# light.net
KiCad netlist of a schematic drawn in EAGLE
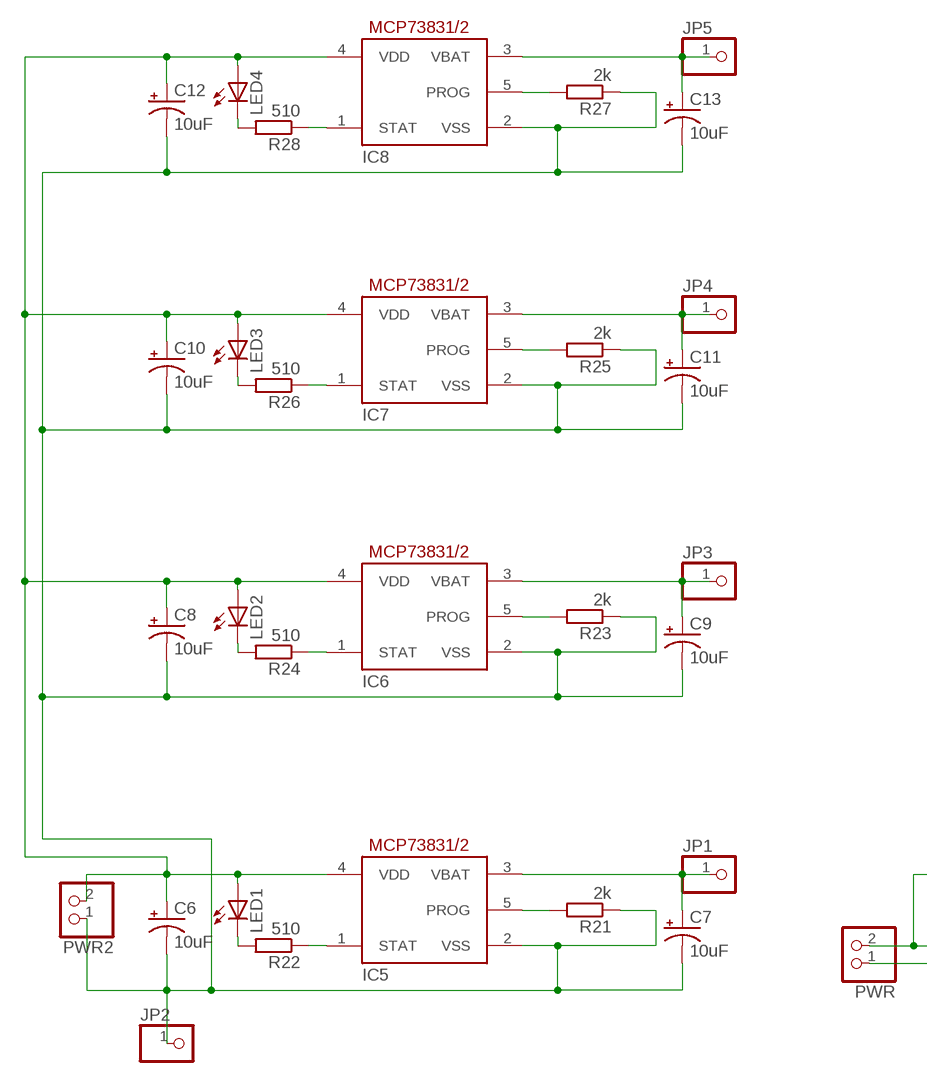
[diagram p0: schematic, sheet 1, part 1 of 2]
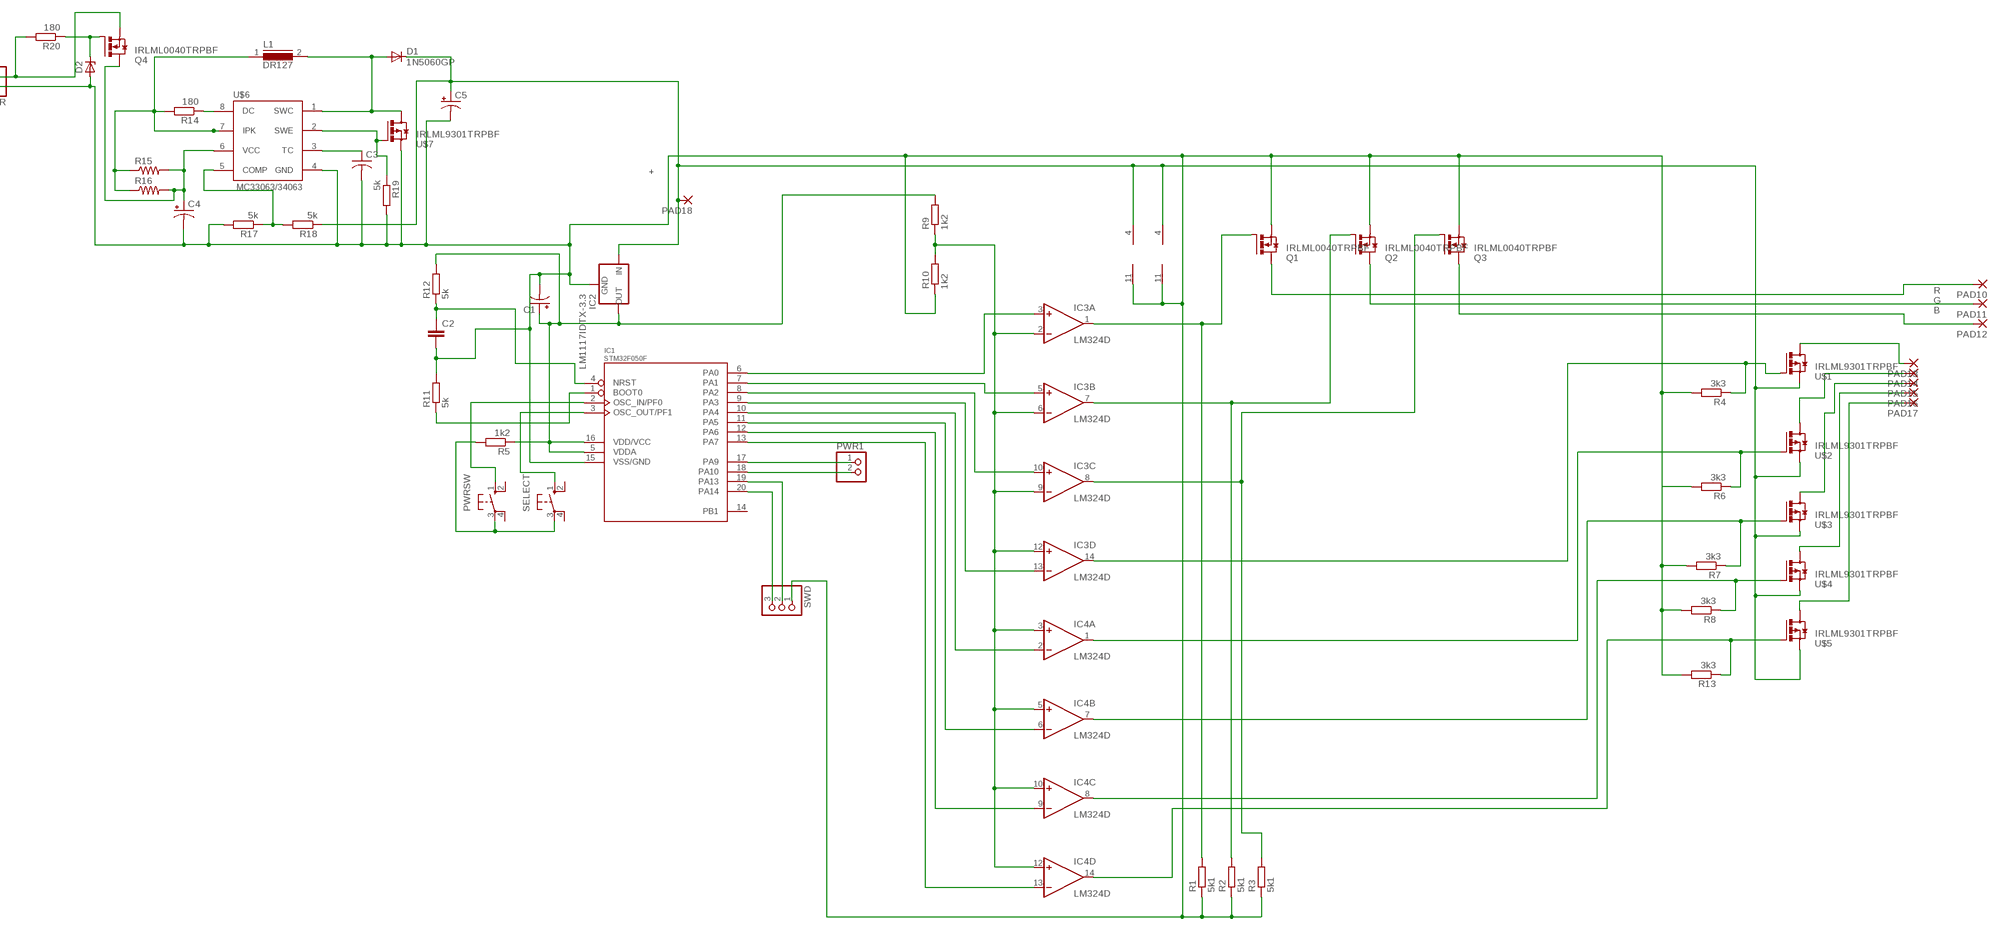
[diagram p1: schematic, sheet 1, part 2 of 2]

(export (version "E")
  (design (tool "Eeschema 10.0.6"))
  (components
    (comp (ref "C1")
      (value "CPOL-USSMCD")
      (footprint "eagle-import:SMC_D")
      (libsource (lib "eagle-import") (part "CPOL-USSMCD"))
    )
    (comp (ref "C2")
      (value "C-EUC1206")
      (footprint "eagle-import:C1206")
      (libsource (lib "eagle-import") (part "C-EUC1206"))
    )
    (comp (ref "C3")
      (value "C-US050-024X044")
      (footprint "eagle-import:C050-024X044")
      (libsource (lib "eagle-import") (part "C-US050-024X044"))
    )
    (comp (ref "C4")
      (value "CPOL-USE5-8.5")
      (footprint "eagle-import:E5-8,5")
      (libsource (lib "eagle-import") (part "CPOL-USE5-8.5"))
    )
    (comp (ref "C5")
      (value "CPOL-USE5-8.5")
      (footprint "eagle-import:E5-8,5")
      (libsource (lib "eagle-import") (part "CPOL-USE5-8.5"))
    )
    (comp (ref "C6")
      (value "10uF")
      (footprint "eagle-import:SMC_D")
      (libsource (lib "eagle-import") (part "CPOL-USSMCD"))
    )
    (comp (ref "C7")
      (value "10uF")
      (footprint "eagle-import:SMC_D")
      (libsource (lib "eagle-import") (part "CPOL-USSMCD"))
    )
    (comp (ref "C8")
      (value "10uF")
      (footprint "eagle-import:SMC_D")
      (libsource (lib "eagle-import") (part "CPOL-USSMCD"))
    )
    (comp (ref "C9")
      (value "10uF")
      (footprint "eagle-import:SMC_D")
      (libsource (lib "eagle-import") (part "CPOL-USSMCD"))
    )
    (comp (ref "C10")
      (value "10uF")
      (footprint "eagle-import:SMC_D")
      (libsource (lib "eagle-import") (part "CPOL-USSMCD"))
    )
    (comp (ref "C11")
      (value "10uF")
      (footprint "eagle-import:SMC_D")
      (libsource (lib "eagle-import") (part "CPOL-USSMCD"))
    )
    (comp (ref "C12")
      (value "10uF")
      (footprint "eagle-import:SMC_D")
      (libsource (lib "eagle-import") (part "CPOL-USSMCD"))
    )
    (comp (ref "C13")
      (value "10uF")
      (footprint "eagle-import:SMC_D")
      (libsource (lib "eagle-import") (part "CPOL-USSMCD"))
    )
    (comp (ref "D1")
      (value "1N5060GP")
      (footprint "eagle-import:DO15-12")
      (libsource (lib "eagle-import") (part "1N5060GP"))
    )
    (comp (ref "D2")
      (value "ZENER-DIODESOD80C")
      (footprint "eagle-import:SOD80C")
      (libsource (lib "eagle-import") (part "ZENER-DIODESOD80C"))
    )
    (comp (ref "IC1")
      (value "STM32F050F")
      (footprint "eagle-import:TSSOP20")
      (libsource (lib "eagle-import") (part "STM32F050F"))
    )
    (comp (ref "IC2")
      (value "LM1117IDTX-3.3")
      (footprint "eagle-import:TO252")
      (libsource (lib "eagle-import") (part "LM1117IDTX-3.3"))
    )
    (comp (ref "IC3")
      (value "LM324D")
      (footprint "eagle-import:SO14")
      (libsource (lib "eagle-import") (part "LM324D"))
    )
    (comp (ref "IC4")
      (value "LM324D")
      (footprint "eagle-import:SO14")
      (libsource (lib "eagle-import") (part "LM324D"))
    )
    (comp (ref "IC5")
      (value "MCP73831/OT")
      (footprint "eagle-import:SOT23-5L")
      (libsource (lib "eagle-import") (part "MCP73831/OT"))
    )
    (comp (ref "IC6")
      (value "MCP73831/OT")
      (footprint "eagle-import:SOT23-5L")
      (libsource (lib "eagle-import") (part "MCP73831/OT"))
    )
    (comp (ref "IC7")
      (value "MCP73831/OT")
      (footprint "eagle-import:SOT23-5L")
      (libsource (lib "eagle-import") (part "MCP73831/OT"))
    )
    (comp (ref "IC8")
      (value "MCP73831/OT")
      (footprint "eagle-import:SOT23-5L")
      (libsource (lib "eagle-import") (part "MCP73831/OT"))
    )
    (comp (ref "JP1")
      (value "PINHD-1X1")
      (footprint "eagle-import:1X01")
      (libsource (lib "eagle-import") (part "PINHD-1X1"))
    )
    (comp (ref "JP2")
      (value "PINHD-1X1")
      (footprint "eagle-import:1X01")
      (libsource (lib "eagle-import") (part "PINHD-1X1"))
    )
    (comp (ref "JP3")
      (value "PINHD-1X1")
      (footprint "eagle-import:1X01")
      (libsource (lib "eagle-import") (part "PINHD-1X1"))
    )
    (comp (ref "JP4")
      (value "PINHD-1X1")
      (footprint "eagle-import:1X01")
      (libsource (lib "eagle-import") (part "PINHD-1X1"))
    )
    (comp (ref "JP5")
      (value "PINHD-1X1")
      (footprint "eagle-import:1X01")
      (libsource (lib "eagle-import") (part "PINHD-1X1"))
    )
    (comp (ref "L1")
      (value "DR127")
      (footprint "eagle-import:DR127")
      (libsource (lib "eagle-import") (part "DR127"))
    )
    (comp (ref "LED1")
      (value "LED")
      (footprint "eagle-import:SMARTLED-TTW")
      (libsource (lib "eagle-import") (part "LED"))
    )
    (comp (ref "LED2")
      (value "LED")
      (footprint "eagle-import:SMARTLED-TTW")
      (libsource (lib "eagle-import") (part "LED"))
    )
    (comp (ref "LED3")
      (value "LED")
      (footprint "eagle-import:SMARTLED-TTW")
      (libsource (lib "eagle-import") (part "LED"))
    )
    (comp (ref "LED4")
      (value "LED")
      (footprint "eagle-import:SMARTLED-TTW")
      (libsource (lib "eagle-import") (part "LED"))
    )
    (comp (ref "PAD10")
      (value "SMD2")
      (footprint "eagle-import:SMD1,27-2,54")
      (libsource (lib "eagle-import") (part "SMD2"))
    )
    (comp (ref "PAD11")
      (value "SMD2")
      (footprint "eagle-import:SMD1,27-2,54")
      (libsource (lib "eagle-import") (part "SMD2"))
    )
    (comp (ref "PAD12")
      (value "SMD2")
      (footprint "eagle-import:SMD1,27-2,54")
      (libsource (lib "eagle-import") (part "SMD2"))
    )
    (comp (ref "PAD13")
      (value "SMD2")
      (footprint "eagle-import:SMD1,27-2,54")
      (libsource (lib "eagle-import") (part "SMD2"))
    )
    (comp (ref "PAD14")
      (value "SMD2")
      (footprint "eagle-import:SMD1,27-2,54")
      (libsource (lib "eagle-import") (part "SMD2"))
    )
    (comp (ref "PAD15")
      (value "SMD2")
      (footprint "eagle-import:SMD1,27-2,54")
      (libsource (lib "eagle-import") (part "SMD2"))
    )
    (comp (ref "PAD16")
      (value "SMD2")
      (footprint "eagle-import:SMD1,27-2,54")
      (libsource (lib "eagle-import") (part "SMD2"))
    )
    (comp (ref "PAD17")
      (value "SMD2")
      (footprint "eagle-import:SMD1,27-2,54")
      (libsource (lib "eagle-import") (part "SMD2"))
    )
    (comp (ref "PAD18")
      (value "SMD2")
      (footprint "eagle-import:SMD1,27-2,54")
      (libsource (lib "eagle-import") (part "SMD2"))
    )
    (comp (ref "PWR")
      (value "PINHD-1X2")
      (footprint "eagle-import:1X02")
      (libsource (lib "eagle-import") (part "PINHD-1X2"))
    )
    (comp (ref "PWR1")
      (value "PINHD-1X2")
      (footprint "eagle-import:1X02")
      (libsource (lib "eagle-import") (part "PINHD-1X2"))
    )
    (comp (ref "PWR2")
      (value "PINHD-1X2")
      (footprint "eagle-import:1X02")
      (libsource (lib "eagle-import") (part "PINHD-1X2"))
    )
    (comp (ref "PWRSW")
      (value "10-XX")
      (footprint "eagle-import:B3F-10XX")
      (fields (field (name "MPN") "B3F-1000"))
      (libsource (lib "eagle-import") (part "10-XX"))
    )
    (comp (ref "Q1")
      (value "IRLML0040TRPBF")
      (footprint "eagle-import:MICRO3")
      (libsource (lib "eagle-import") (part "IRLML0040TRPBF"))
    )
    (comp (ref "Q2")
      (value "IRLML0040TRPBF")
      (footprint "eagle-import:MICRO3")
      (libsource (lib "eagle-import") (part "IRLML0040TRPBF"))
    )
    (comp (ref "Q3")
      (value "IRLML0040TRPBF")
      (footprint "eagle-import:MICRO3")
      (libsource (lib "eagle-import") (part "IRLML0040TRPBF"))
    )
    (comp (ref "Q4")
      (value "IRLML0040TRPBF")
      (footprint "eagle-import:MICRO3")
      (libsource (lib "eagle-import") (part "IRLML0040TRPBF"))
    )
    (comp (ref "R1")
      (value "5k1")
      (footprint "eagle-import:M1206")
      (libsource (lib "eagle-import") (part "R-EU_M1206"))
    )
    (comp (ref "R2")
      (value "5k1")
      (footprint "eagle-import:M1206")
      (libsource (lib "eagle-import") (part "R-EU_M1206"))
    )
    (comp (ref "R3")
      (value "5k1")
      (footprint "eagle-import:M1206")
      (libsource (lib "eagle-import") (part "R-EU_M1206"))
    )
    (comp (ref "R4")
      (value "3k3")
      (footprint "eagle-import:M1206")
      (libsource (lib "eagle-import") (part "R-EU_M1206"))
    )
    (comp (ref "R5")
      (value "1k2")
      (footprint "eagle-import:M1206")
      (libsource (lib "eagle-import") (part "R-EU_M1206"))
    )
    (comp (ref "R6")
      (value "3k3")
      (footprint "eagle-import:M1206")
      (libsource (lib "eagle-import") (part "R-EU_M1206"))
    )
    (comp (ref "R7")
      (value "3k3")
      (footprint "eagle-import:M1206")
      (libsource (lib "eagle-import") (part "R-EU_M1206"))
    )
    (comp (ref "R8")
      (value "3k3")
      (footprint "eagle-import:M1206")
      (libsource (lib "eagle-import") (part "R-EU_M1206"))
    )
    (comp (ref "R9")
      (value "1k2")
      (footprint "eagle-import:M1206")
      (libsource (lib "eagle-import") (part "R-EU_M1206"))
    )
    (comp (ref "R10")
      (value "1k2")
      (footprint "eagle-import:M1206")
      (libsource (lib "eagle-import") (part "R-EU_M1206"))
    )
    (comp (ref "R11")
      (value "5k")
      (footprint "eagle-import:M1206")
      (libsource (lib "eagle-import") (part "R-EU_M1206"))
    )
    (comp (ref "R12")
      (value "5k")
      (footprint "eagle-import:M1206")
      (libsource (lib "eagle-import") (part "R-EU_M1206"))
    )
    (comp (ref "R13")
      (value "3k3")
      (footprint "eagle-import:M1206")
      (libsource (lib "eagle-import") (part "R-EU_M1206"))
    )
    (comp (ref "R14")
      (value "180")
      (footprint "eagle-import:M1206")
      (libsource (lib "eagle-import") (part "R-EU_M1206"))
    )
    (comp (ref "R15")
      (value "R-US_0207/12")
      (footprint "eagle-import:0207_12")
      (libsource (lib "eagle-import") (part "R-US_0207/12"))
    )
    (comp (ref "R16")
      (value "R-US_0207/12")
      (footprint "eagle-import:0207_12")
      (libsource (lib "eagle-import") (part "R-US_0207/12"))
    )
    (comp (ref "R17")
      (value "5k")
      (footprint "eagle-import:M1206")
      (libsource (lib "eagle-import") (part "R-EU_M1206"))
    )
    (comp (ref "R18")
      (value "5k")
      (footprint "eagle-import:M1206")
      (libsource (lib "eagle-import") (part "R-EU_M1206"))
    )
    (comp (ref "R19")
      (value "5k")
      (footprint "eagle-import:M1206")
      (libsource (lib "eagle-import") (part "R-EU_M1206"))
    )
    (comp (ref "R20")
      (value "180")
      (footprint "eagle-import:M1206")
      (libsource (lib "eagle-import") (part "R-EU_M1206"))
    )
    (comp (ref "R21")
      (value "2k")
      (footprint "eagle-import:M1206")
      (libsource (lib "eagle-import") (part "R-EU_M1206"))
    )
    (comp (ref "R22")
      (value "510")
      (footprint "eagle-import:M1206")
      (libsource (lib "eagle-import") (part "R-EU_M1206"))
    )
    (comp (ref "R23")
      (value "2k")
      (footprint "eagle-import:M1206")
      (libsource (lib "eagle-import") (part "R-EU_M1206"))
    )
    (comp (ref "R24")
      (value "510")
      (footprint "eagle-import:M1206")
      (libsource (lib "eagle-import") (part "R-EU_M1206"))
    )
    (comp (ref "R25")
      (value "2k")
      (footprint "eagle-import:M1206")
      (libsource (lib "eagle-import") (part "R-EU_M1206"))
    )
    (comp (ref "R26")
      (value "510")
      (footprint "eagle-import:M1206")
      (libsource (lib "eagle-import") (part "R-EU_M1206"))
    )
    (comp (ref "R27")
      (value "2k")
      (footprint "eagle-import:M1206")
      (libsource (lib "eagle-import") (part "R-EU_M1206"))
    )
    (comp (ref "R28")
      (value "510")
      (footprint "eagle-import:M1206")
      (libsource (lib "eagle-import") (part "R-EU_M1206"))
    )
    (comp (ref "SELECT")
      (value "10-XX")
      (footprint "eagle-import:B3F-10XX")
      (fields (field (name "MPN") "B3F-1000"))
      (libsource (lib "eagle-import") (part "10-XX"))
    )
    (comp (ref "SWD")
      (value "PINHD-1X3")
      (footprint "eagle-import:1X03")
      (libsource (lib "eagle-import") (part "PINHD-1X3"))
    )
    (comp (ref "U$1")
      (value "IRLML9301TRPBF")
      (footprint "eagle-import:MICRO3")
      (libsource (lib "eagle-import") (part "IRLML9301TRPBF"))
    )
    (comp (ref "U$2")
      (value "IRLML9301TRPBF")
      (footprint "eagle-import:MICRO3")
      (libsource (lib "eagle-import") (part "IRLML9301TRPBF"))
    )
    (comp (ref "U$3")
      (value "IRLML9301TRPBF")
      (footprint "eagle-import:MICRO3")
      (libsource (lib "eagle-import") (part "IRLML9301TRPBF"))
    )
    (comp (ref "U$4")
      (value "IRLML9301TRPBF")
      (footprint "eagle-import:MICRO3")
      (libsource (lib "eagle-import") (part "IRLML9301TRPBF"))
    )
    (comp (ref "U$5")
      (value "IRLML9301TRPBF")
      (footprint "eagle-import:MICRO3")
      (libsource (lib "eagle-import") (part "IRLML9301TRPBF"))
    )
    (comp (ref "U$6")
      (value "MC33063/MC34063D")
      (footprint "eagle-import:SO08")
      (libsource (lib "eagle-import") (part "MC33063/MC34063D"))
    )
    (comp (ref "U$7")
      (value "IRLML9301TRPBF")
      (footprint "eagle-import:MICRO3")
      (libsource (lib "eagle-import") (part "IRLML9301TRPBF"))
    )
  )
  (nets
    (net (code "1") (name "Net-(IC1-BOOT0)") (class "Default")
      (node (ref "IC1") (pin "1") (pinfunction "BOOT0_1") (pintype "bidirectional"))
      (node (ref "R11") (pin "1") (pinfunction "1_1") (pintype "passive"))
    )
    (net (code "2") (name "Net-(IC1-NRST)") (class "Default")
      (node (ref "C2") (pin "1") (pinfunction "1_1") (pintype "passive"))
      (node (ref "IC1") (pin "4") (pinfunction "NRST_4") (pintype "bidirectional"))
      (node (ref "R12") (pin "1") (pinfunction "1_1") (pintype "passive"))
    )
    (net (code "3") (name "Net-(IC1-OSC_IN{slash}PF0)") (class "Default")
      (node (ref "IC1") (pin "2") (pinfunction "OSC_IN/PF0_2") (pintype "bidirectional"))
      (node (ref "PWRSW") (pin "1") (pinfunction "S_1") (pintype "passive"))
    )
    (net (code "4") (name "Net-(IC1-OSC_OUT{slash}PF1)") (class "Default")
      (node (ref "IC1") (pin "3") (pinfunction "OSC_OUT/PF1_3") (pintype "bidirectional"))
      (node (ref "SELECT") (pin "1") (pinfunction "S_1") (pintype "passive"))
    )
    (net (code "5") (name "Net-(IC1-PA0)") (class "Default")
      (node (ref "IC1") (pin "6") (pinfunction "PA0_6") (pintype "bidirectional"))
      (node (ref "IC3") (pin "3") (pinfunction "+IN_3") (pintype "input"))
    )
    (net (code "6") (name "Net-(IC1-PA1)") (class "Default")
      (node (ref "IC1") (pin "7") (pinfunction "PA1_7") (pintype "bidirectional"))
      (node (ref "IC3") (pin "5") (pinfunction "+IN_5") (pintype "input"))
    )
    (net (code "7") (name "Net-(IC1-PA2)") (class "Default")
      (node (ref "IC1") (pin "8") (pinfunction "PA2_8") (pintype "bidirectional"))
      (node (ref "IC3") (pin "10") (pinfunction "+IN_10") (pintype "input"))
    )
    (net (code "8") (name "Net-(IC1-PA3)") (class "Default")
      (node (ref "IC1") (pin "9") (pinfunction "PA3_9") (pintype "bidirectional"))
      (node (ref "IC3") (pin "13") (pinfunction "-IN_13") (pintype "input"))
    )
    (net (code "9") (name "Net-(IC1-PA4)") (class "Default")
      (node (ref "IC1") (pin "10") (pinfunction "PA4_10") (pintype "bidirectional"))
      (node (ref "IC4") (pin "2") (pinfunction "-IN_2") (pintype "input"))
    )
    (net (code "10") (name "Net-(IC1-PA5)") (class "Default")
      (node (ref "IC1") (pin "11") (pinfunction "PA5_11") (pintype "bidirectional"))
      (node (ref "IC4") (pin "6") (pinfunction "-IN_6") (pintype "input"))
    )
    (net (code "11") (name "Net-(IC1-PA6)") (class "Default")
      (node (ref "IC1") (pin "12") (pinfunction "PA6_12") (pintype "bidirectional"))
      (node (ref "IC4") (pin "9") (pinfunction "-IN_9") (pintype "input"))
    )
    (net (code "12") (name "Net-(IC1-PA7)") (class "Default")
      (node (ref "IC1") (pin "13") (pinfunction "PA7_13") (pintype "bidirectional"))
      (node (ref "IC4") (pin "13") (pinfunction "-IN_13") (pintype "input"))
    )
    (net (code "13") (name "Net-(IC1-PA9)") (class "Default")
      (node (ref "IC1") (pin "17") (pinfunction "PA9_17") (pintype "bidirectional"))
      (node (ref "PWR1") (pin "1") (pinfunction "1_1") (pintype "passive"))
    )
    (net (code "14") (name "Net-(IC1-PA10)") (class "Default")
      (node (ref "IC1") (pin "18") (pinfunction "PA10_18") (pintype "bidirectional"))
      (node (ref "PWR1") (pin "2") (pinfunction "2_2") (pintype "passive"))
    )
    (net (code "15") (name "Net-(IC1-PA13)") (class "Default")
      (node (ref "IC1") (pin "19") (pinfunction "PA13_19") (pintype "bidirectional"))
      (node (ref "SWD") (pin "2") (pinfunction "2_2") (pintype "passive"))
    )
    (net (code "16") (name "Net-(IC1-PA14)") (class "Default")
      (node (ref "IC1") (pin "20") (pinfunction "PA14_20") (pintype "bidirectional"))
      (node (ref "SWD") (pin "3") (pinfunction "3_3") (pintype "passive"))
    )
    (net (code "17") (name "Net-(IC1-VDDA)") (class "Default")
      (node (ref "C1") (pin "+") (pinfunction "+_+") (pintype "passive"))
      (node (ref "IC1") (pin "16") (pinfunction "VDD/VCC_16") (pintype "power_in"))
      (node (ref "IC1") (pin "5") (pinfunction "VDDA_5") (pintype "power_in"))
      (node (ref "IC2") (pin "TAB") (pinfunction "OUT_TAB") (pintype "passive"))
      (node (ref "R12") (pin "2") (pinfunction "2_2") (pintype "passive"))
      (node (ref "R5") (pin "1") (pinfunction "1_1") (pintype "passive"))
      (node (ref "R9") (pin "2") (pinfunction "2_2") (pintype "passive"))
    )
    (net (code "18") (name "Net-(IC1-VSS{slash}GND)") (class "Default")
      (node (ref "C1") (pin "-") (pinfunction "-_-") (pintype "passive"))
      (node (ref "C2") (pin "2") (pinfunction "2_2") (pintype "passive"))
      (node (ref "C3") (pin "2") (pinfunction "2_2") (pintype "passive"))
      (node (ref "C4") (pin "-") (pinfunction "-_-") (pintype "passive"))
      (node (ref "C5") (pin "-") (pinfunction "-_-") (pintype "passive"))
      (node (ref "D2") (pin "A") (pinfunction "A_A") (pintype "passive"))
      (node (ref "IC1") (pin "15") (pinfunction "VSS/GND_15") (pintype "power_in"))
      (node (ref "IC2") (pin "1") (pinfunction "GND_1") (pintype "input"))
      (node (ref "IC3") (pin "11") (pinfunction "V-_11") (pintype "power_in"))
      (node (ref "IC4") (pin "11") (pinfunction "V-_11") (pintype "power_in"))
      (node (ref "PWR") (pin "1") (pinfunction "1_1") (pintype "passive"))
      (node (ref "Q1") (pin "2") (pinfunction "S_2") (pintype "passive"))
      (node (ref "Q2") (pin "2") (pinfunction "S_2") (pintype "passive"))
      (node (ref "Q3") (pin "2") (pinfunction "S_2") (pintype "passive"))
      (node (ref "R1") (pin "1") (pinfunction "1_1") (pintype "passive"))
      (node (ref "R10") (pin "1") (pinfunction "1_1") (pintype "passive"))
      (node (ref "R11") (pin "2") (pinfunction "2_2") (pintype "passive"))
      (node (ref "R13") (pin "2") (pinfunction "2_2") (pintype "passive"))
      (node (ref "R17") (pin "2") (pinfunction "2_2") (pintype "passive"))
      (node (ref "R19") (pin "2") (pinfunction "2_2") (pintype "passive"))
      (node (ref "R2") (pin "1") (pinfunction "1_1") (pintype "passive"))
      (node (ref "R3") (pin "1") (pinfunction "1_1") (pintype "passive"))
      (node (ref "R4") (pin "2") (pinfunction "2_2") (pintype "passive"))
      (node (ref "R6") (pin "2") (pinfunction "2_2") (pintype "passive"))
      (node (ref "R7") (pin "2") (pinfunction "2_2") (pintype "passive"))
      (node (ref "R8") (pin "2") (pinfunction "2_2") (pintype "passive"))
      (node (ref "SWD") (pin "1") (pinfunction "1_1") (pintype "passive"))
      (node (ref "U$6") (pin "4") (pinfunction "GND_4") (pintype "power_in"))
      (node (ref "U$7") (pin "2") (pinfunction "S_2") (pintype "passive"))
    )
    (net (code "19") (name "Net-(IC2-IN)") (class "Default")
      (node (ref "C5") (pin "+") (pinfunction "+_+") (pintype "passive"))
      (node (ref "D1") (pin "C") (pinfunction "C_C") (pintype "passive"))
      (node (ref "IC2") (pin "2") (pinfunction "IN_2") (pintype "input"))
      (node (ref "IC3") (pin "4") (pinfunction "V+_4") (pintype "power_in"))
      (node (ref "IC4") (pin "4") (pinfunction "V+_4") (pintype "power_in"))
      (node (ref "PAD18") (pin "1") (pinfunction "P_1") (pintype "passive"))
      (node (ref "R18") (pin "1") (pinfunction "1_1") (pintype "passive"))
      (node (ref "U$1") (pin "2") (pinfunction "S_2") (pintype "passive"))
      (node (ref "U$2") (pin "2") (pinfunction "S_2") (pintype "passive"))
      (node (ref "U$3") (pin "2") (pinfunction "S_2") (pintype "passive"))
      (node (ref "U$4") (pin "2") (pinfunction "S_2") (pintype "passive"))
      (node (ref "U$5") (pin "2") (pinfunction "S_2") (pintype "passive"))
    )
    (net (code "20") (name "Net-(IC3A--IN)") (class "Default")
      (node (ref "IC3") (pin "12") (pinfunction "+IN_12") (pintype "input"))
      (node (ref "IC3") (pin "2") (pinfunction "-IN_2") (pintype "input"))
      (node (ref "IC3") (pin "6") (pinfunction "-IN_6") (pintype "input"))
      (node (ref "IC3") (pin "9") (pinfunction "-IN_9") (pintype "input"))
      (node (ref "IC4") (pin "10") (pinfunction "+IN_10") (pintype "input"))
      (node (ref "IC4") (pin "12") (pinfunction "+IN_12") (pintype "input"))
      (node (ref "IC4") (pin "3") (pinfunction "+IN_3") (pintype "input"))
      (node (ref "IC4") (pin "5") (pinfunction "+IN_5") (pintype "input"))
      (node (ref "R10") (pin "2") (pinfunction "2_2") (pintype "passive"))
      (node (ref "R9") (pin "1") (pinfunction "1_1") (pintype "passive"))
    )
    (net (code "21") (name "Net-(IC3A-OUT)") (class "Default")
      (node (ref "IC3") (pin "1") (pinfunction "OUT_1") (pintype "output"))
      (node (ref "Q1") (pin "1") (pinfunction "G_1") (pintype "passive"))
      (node (ref "R1") (pin "2") (pinfunction "2_2") (pintype "passive"))
    )
    (net (code "22") (name "Net-(IC3B-OUT)") (class "Default")
      (node (ref "IC3") (pin "7") (pinfunction "OUT_7") (pintype "output"))
      (node (ref "Q2") (pin "1") (pinfunction "G_1") (pintype "passive"))
      (node (ref "R2") (pin "2") (pinfunction "2_2") (pintype "passive"))
    )
    (net (code "23") (name "Net-(IC3C-OUT)") (class "Default")
      (node (ref "IC3") (pin "8") (pinfunction "OUT_8") (pintype "output"))
      (node (ref "Q3") (pin "1") (pinfunction "G_1") (pintype "passive"))
      (node (ref "R3") (pin "2") (pinfunction "2_2") (pintype "passive"))
    )
    (net (code "24") (name "Net-(IC3D-OUT)") (class "Default")
      (node (ref "IC3") (pin "14") (pinfunction "OUT_14") (pintype "output"))
      (node (ref "R4") (pin "1") (pinfunction "1_1") (pintype "passive"))
      (node (ref "U$1") (pin "1") (pinfunction "G_1") (pintype "passive"))
    )
    (net (code "25") (name "Net-(IC4A-OUT)") (class "Default")
      (node (ref "IC4") (pin "1") (pinfunction "OUT_1") (pintype "output"))
      (node (ref "R6") (pin "1") (pinfunction "1_1") (pintype "passive"))
      (node (ref "U$2") (pin "1") (pinfunction "G_1") (pintype "passive"))
    )
    (net (code "26") (name "Net-(IC4B-OUT)") (class "Default")
      (node (ref "IC4") (pin "7") (pinfunction "OUT_7") (pintype "output"))
      (node (ref "R7") (pin "1") (pinfunction "1_1") (pintype "passive"))
      (node (ref "U$3") (pin "1") (pinfunction "G_1") (pintype "passive"))
    )
    (net (code "27") (name "Net-(IC4C-OUT)") (class "Default")
      (node (ref "IC4") (pin "8") (pinfunction "OUT_8") (pintype "output"))
      (node (ref "R8") (pin "1") (pinfunction "1_1") (pintype "passive"))
      (node (ref "U$4") (pin "1") (pinfunction "G_1") (pintype "passive"))
    )
    (net (code "28") (name "Net-(IC4D-OUT)") (class "Default")
      (node (ref "IC4") (pin "14") (pinfunction "OUT_14") (pintype "output"))
      (node (ref "R13") (pin "1") (pinfunction "1_1") (pintype "passive"))
      (node (ref "U$5") (pin "1") (pinfunction "G_1") (pintype "passive"))
    )
    (net (code "29") (name "Net-(IC5-PROG)") (class "Default")
      (node (ref "IC5") (pin "5") (pinfunction "PROG_5") (pintype "input"))
      (node (ref "R21") (pin "2") (pinfunction "2_2") (pintype "passive"))
    )
    (net (code "30") (name "Net-(IC5-STAT)") (class "Default")
      (node (ref "IC5") (pin "1") (pinfunction "STAT_1") (pintype "output"))
      (node (ref "R22") (pin "1") (pinfunction "1_1") (pintype "passive"))
    )
    (net (code "31") (name "Net-(IC5-VBAT)") (class "Default")
      (node (ref "C7") (pin "+") (pinfunction "+_+") (pintype "passive"))
      (node (ref "IC5") (pin "3") (pinfunction "VBAT_3") (pintype "bidirectional"))
      (node (ref "JP1") (pin "1") (pinfunction "1_1") (pintype "passive"))
    )
    (net (code "32") (name "Net-(IC5-VDD)") (class "Default")
      (node (ref "C10") (pin "+") (pinfunction "+_+") (pintype "passive"))
      (node (ref "C12") (pin "+") (pinfunction "+_+") (pintype "passive"))
      (node (ref "C6") (pin "+") (pinfunction "+_+") (pintype "passive"))
      (node (ref "C8") (pin "+") (pinfunction "+_+") (pintype "passive"))
      (node (ref "IC5") (pin "4") (pinfunction "VDD_4") (pintype "power_in"))
      (node (ref "IC6") (pin "4") (pinfunction "VDD_4") (pintype "power_in"))
      (node (ref "IC7") (pin "4") (pinfunction "VDD_4") (pintype "power_in"))
      (node (ref "IC8") (pin "4") (pinfunction "VDD_4") (pintype "power_in"))
      (node (ref "LED1") (pin "A@1") (pinfunction "A_A@1") (pintype "passive"))
      (node (ref "LED2") (pin "A@1") (pinfunction "A_A@1") (pintype "passive"))
      (node (ref "LED3") (pin "A@1") (pinfunction "A_A@1") (pintype "passive"))
      (node (ref "LED4") (pin "A@1") (pinfunction "A_A@1") (pintype "passive"))
      (node (ref "PWR2") (pin "2") (pinfunction "2_2") (pintype "passive"))
    )
    (net (code "33") (name "Net-(IC5-VSS)") (class "Default")
      (node (ref "C10") (pin "-") (pinfunction "-_-") (pintype "passive"))
      (node (ref "C11") (pin "-") (pinfunction "-_-") (pintype "passive"))
      (node (ref "C12") (pin "-") (pinfunction "-_-") (pintype "passive"))
      (node (ref "C13") (pin "-") (pinfunction "-_-") (pintype "passive"))
      (node (ref "C6") (pin "-") (pinfunction "-_-") (pintype "passive"))
      (node (ref "C7") (pin "-") (pinfunction "-_-") (pintype "passive"))
      (node (ref "C8") (pin "-") (pinfunction "-_-") (pintype "passive"))
      (node (ref "C9") (pin "-") (pinfunction "-_-") (pintype "passive"))
      (node (ref "IC5") (pin "2") (pinfunction "VSS_2") (pintype "power_in"))
      (node (ref "IC6") (pin "2") (pinfunction "VSS_2") (pintype "power_in"))
      (node (ref "IC7") (pin "2") (pinfunction "VSS_2") (pintype "power_in"))
      (node (ref "IC8") (pin "2") (pinfunction "VSS_2") (pintype "power_in"))
      (node (ref "JP2") (pin "1") (pinfunction "1_1") (pintype "passive"))
      (node (ref "PWR2") (pin "1") (pinfunction "1_1") (pintype "passive"))
      (node (ref "R21") (pin "1") (pinfunction "1_1") (pintype "passive"))
      (node (ref "R23") (pin "1") (pinfunction "1_1") (pintype "passive"))
      (node (ref "R25") (pin "1") (pinfunction "1_1") (pintype "passive"))
      (node (ref "R27") (pin "1") (pinfunction "1_1") (pintype "passive"))
    )
    (net (code "34") (name "Net-(IC6-PROG)") (class "Default")
      (node (ref "IC6") (pin "5") (pinfunction "PROG_5") (pintype "input"))
      (node (ref "R23") (pin "2") (pinfunction "2_2") (pintype "passive"))
    )
    (net (code "35") (name "Net-(IC6-STAT)") (class "Default")
      (node (ref "IC6") (pin "1") (pinfunction "STAT_1") (pintype "output"))
      (node (ref "R24") (pin "1") (pinfunction "1_1") (pintype "passive"))
    )
    (net (code "36") (name "Net-(IC6-VBAT)") (class "Default")
      (node (ref "C9") (pin "+") (pinfunction "+_+") (pintype "passive"))
      (node (ref "IC6") (pin "3") (pinfunction "VBAT_3") (pintype "bidirectional"))
      (node (ref "JP3") (pin "1") (pinfunction "1_1") (pintype "passive"))
    )
    (net (code "37") (name "Net-(IC7-PROG)") (class "Default")
      (node (ref "IC7") (pin "5") (pinfunction "PROG_5") (pintype "input"))
      (node (ref "R25") (pin "2") (pinfunction "2_2") (pintype "passive"))
    )
    (net (code "38") (name "Net-(IC7-STAT)") (class "Default")
      (node (ref "IC7") (pin "1") (pinfunction "STAT_1") (pintype "output"))
      (node (ref "R26") (pin "1") (pinfunction "1_1") (pintype "passive"))
    )
    (net (code "39") (name "Net-(IC7-VBAT)") (class "Default")
      (node (ref "C11") (pin "+") (pinfunction "+_+") (pintype "passive"))
      (node (ref "IC7") (pin "3") (pinfunction "VBAT_3") (pintype "bidirectional"))
      (node (ref "JP4") (pin "1") (pinfunction "1_1") (pintype "passive"))
    )
    (net (code "40") (name "Net-(IC8-PROG)") (class "Default")
      (node (ref "IC8") (pin "5") (pinfunction "PROG_5") (pintype "input"))
      (node (ref "R27") (pin "2") (pinfunction "2_2") (pintype "passive"))
    )
    (net (code "41") (name "Net-(IC8-STAT)") (class "Default")
      (node (ref "IC8") (pin "1") (pinfunction "STAT_1") (pintype "output"))
      (node (ref "R28") (pin "1") (pinfunction "1_1") (pintype "passive"))
    )
    (net (code "42") (name "Net-(IC8-VBAT)") (class "Default")
      (node (ref "C13") (pin "+") (pinfunction "+_+") (pintype "passive"))
      (node (ref "IC8") (pin "3") (pinfunction "VBAT_3") (pintype "bidirectional"))
      (node (ref "JP5") (pin "1") (pinfunction "1_1") (pintype "passive"))
    )
    (net (code "43") (name "Net-(LED1-C)") (class "Default")
      (node (ref "LED1") (pin "C@1") (pinfunction "C_C@1") (pintype "passive"))
      (node (ref "R22") (pin "2") (pinfunction "2_2") (pintype "passive"))
    )
    (net (code "44") (name "Net-(LED2-C)") (class "Default")
      (node (ref "LED2") (pin "C@1") (pinfunction "C_C@1") (pintype "passive"))
      (node (ref "R24") (pin "2") (pinfunction "2_2") (pintype "passive"))
    )
    (net (code "45") (name "Net-(LED3-C)") (class "Default")
      (node (ref "LED3") (pin "C@1") (pinfunction "C_C@1") (pintype "passive"))
      (node (ref "R26") (pin "2") (pinfunction "2_2") (pintype "passive"))
    )
    (net (code "46") (name "Net-(LED4-C)") (class "Default")
      (node (ref "LED4") (pin "C@1") (pinfunction "C_C@1") (pintype "passive"))
      (node (ref "R28") (pin "2") (pinfunction "2_2") (pintype "passive"))
    )
    (net (code "47") (name "Net-(PAD10-P)") (class "Default")
      (node (ref "PAD10") (pin "1") (pinfunction "P_1") (pintype "passive"))
      (node (ref "Q1") (pin "3") (pinfunction "D_3") (pintype "passive"))
    )
    (net (code "48") (name "Net-(PAD11-P)") (class "Default")
      (node (ref "PAD11") (pin "1") (pinfunction "P_1") (pintype "passive"))
      (node (ref "Q2") (pin "3") (pinfunction "D_3") (pintype "passive"))
    )
    (net (code "49") (name "Net-(PAD12-P)") (class "Default")
      (node (ref "PAD12") (pin "1") (pinfunction "P_1") (pintype "passive"))
      (node (ref "Q3") (pin "3") (pinfunction "D_3") (pintype "passive"))
    )
    (net (code "50") (name "Net-(PAD13-P)") (class "Default")
      (node (ref "PAD13") (pin "1") (pinfunction "P_1") (pintype "passive"))
      (node (ref "U$1") (pin "3") (pinfunction "D_3") (pintype "passive"))
    )
    (net (code "51") (name "Net-(PAD14-P)") (class "Default")
      (node (ref "PAD14") (pin "1") (pinfunction "P_1") (pintype "passive"))
      (node (ref "U$2") (pin "3") (pinfunction "D_3") (pintype "passive"))
    )
    (net (code "52") (name "Net-(PAD15-P)") (class "Default")
      (node (ref "PAD15") (pin "1") (pinfunction "P_1") (pintype "passive"))
      (node (ref "U$3") (pin "3") (pinfunction "D_3") (pintype "passive"))
    )
    (net (code "53") (name "Net-(PAD16-P)") (class "Default")
      (node (ref "PAD16") (pin "1") (pinfunction "P_1") (pintype "passive"))
      (node (ref "U$4") (pin "3") (pinfunction "D_3") (pintype "passive"))
    )
    (net (code "54") (name "Net-(PAD17-P)") (class "Default")
      (node (ref "PAD17") (pin "1") (pinfunction "P_1") (pintype "passive"))
      (node (ref "U$5") (pin "3") (pinfunction "D_3") (pintype "passive"))
    )
    (net (code "55") (name "Net-(PWRSW-P)") (class "Default")
      (node (ref "PWRSW") (pin "3") (pinfunction "P_3") (pintype "passive"))
      (node (ref "R5") (pin "2") (pinfunction "2_2") (pintype "passive"))
      (node (ref "SELECT") (pin "3") (pinfunction "P_3") (pintype "passive"))
    )
    (net (code "56") (name "Net-(Q4-D)") (class "Default")
      (node (ref "C4") (pin "+") (pinfunction "+_+") (pintype "passive"))
      (node (ref "Q4") (pin "3") (pinfunction "D_3") (pintype "passive"))
      (node (ref "R15") (pin "2") (pinfunction "2_2") (pintype "passive"))
      (node (ref "R16") (pin "2") (pinfunction "2_2") (pintype "passive"))
      (node (ref "U$6") (pin "6") (pinfunction "VCC_6") (pintype "power_in"))
    )
    (net (code "57") (name "Net-(Q4-G)") (class "Default")
      (node (ref "D2") (pin "C") (pinfunction "C_C") (pintype "passive"))
      (node (ref "Q4") (pin "1") (pinfunction "G_1") (pintype "passive"))
      (node (ref "R20") (pin "1") (pinfunction "1_1") (pintype "passive"))
    )
    (net (code "58") (name "Net-(Q4-S)") (class "Default")
      (node (ref "PWR") (pin "2") (pinfunction "2_2") (pintype "passive"))
      (node (ref "Q4") (pin "2") (pinfunction "S_2") (pintype "passive"))
      (node (ref "R20") (pin "2") (pinfunction "2_2") (pintype "passive"))
    )
    (net (code "59") (name "Net-(U$6-COMP)") (class "Default")
      (node (ref "R17") (pin "1") (pinfunction "1_1") (pintype "passive"))
      (node (ref "R18") (pin "2") (pinfunction "2_2") (pintype "passive"))
      (node (ref "U$6") (pin "5") (pinfunction "COMP_5") (pintype "input"))
    )
    (net (code "60") (name "Net-(U$6-DC)") (class "Default")
      (node (ref "R14") (pin "1") (pinfunction "1_1") (pintype "passive"))
      (node (ref "U$6") (pin "8") (pinfunction "DC_8") (pintype "input"))
    )
    (net (code "61") (name "Net-(U$6-IPK)") (class "Default")
      (node (ref "L1") (pin "1") (pinfunction "1_1") (pintype "passive"))
      (node (ref "R14") (pin "2") (pinfunction "2_2") (pintype "passive"))
      (node (ref "R15") (pin "1") (pinfunction "1_1") (pintype "passive"))
      (node (ref "R16") (pin "1") (pinfunction "1_1") (pintype "passive"))
      (node (ref "U$6") (pin "7") (pinfunction "IPK_7") (pintype "bidirectional"))
    )
    (net (code "62") (name "Net-(U$6-SWC)") (class "Default")
      (node (ref "D1") (pin "A") (pinfunction "A_A") (pintype "passive"))
      (node (ref "L1") (pin "2") (pinfunction "2_2") (pintype "passive"))
      (node (ref "U$6") (pin "1") (pinfunction "SWC_1") (pintype "input"))
      (node (ref "U$7") (pin "3") (pinfunction "D_3") (pintype "passive"))
    )
    (net (code "63") (name "Net-(U$6-SWE)") (class "Default")
      (node (ref "R19") (pin "1") (pinfunction "1_1") (pintype "passive"))
      (node (ref "U$6") (pin "2") (pinfunction "SWE_2") (pintype "input"))
      (node (ref "U$7") (pin "1") (pinfunction "G_1") (pintype "passive"))
    )
    (net (code "64") (name "Net-(U$6-TC)") (class "Default")
      (node (ref "C3") (pin "1") (pinfunction "1_1") (pintype "passive"))
      (node (ref "U$6") (pin "3") (pinfunction "TC_3") (pintype "input"))
    )
    (net (code "65") (name "unconnected-(IC1-PB1-Pad14)") (class "Default")
      (node (ref "IC1") (pin "14") (pinfunction "PB1_14") (pintype "bidirectional"))
    )
    (net (code "66") (name "unconnected-(PWRSW-P1-Pad4)") (class "Default")
      (node (ref "PWRSW") (pin "4") (pinfunction "P1_4") (pintype "passive"))
    )
    (net (code "67") (name "unconnected-(PWRSW-S1-Pad2)") (class "Default")
      (node (ref "PWRSW") (pin "2") (pinfunction "S1_2") (pintype "passive"))
    )
    (net (code "68") (name "unconnected-(SELECT-P1-Pad4)") (class "Default")
      (node (ref "SELECT") (pin "4") (pinfunction "P1_4") (pintype "passive"))
    )
    (net (code "69") (name "unconnected-(SELECT-S1-Pad2)") (class "Default")
      (node (ref "SELECT") (pin "2") (pinfunction "S1_2") (pintype "passive"))
    )
  )
)
